# Eeprom.net
KiCad netlist of a schematic drawn in Altium Designer
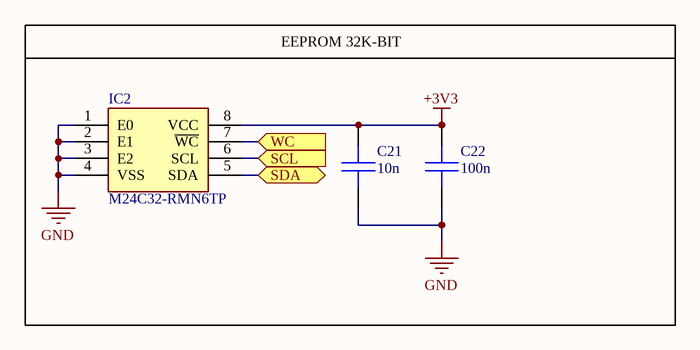
[diagram p0: Eeprom.SchDoc]

(export (version "E")
  (design (tool "Eeschema 10.0.6"))
  (components
    (comp (ref "C21")
      (value "10n")
      (footprint "C_0603")
      (description "SMD Chip Capacitor")
      (libsource (lib "My_Integrated_Lib") (part "CAP"))
    )
    (comp (ref "C22")
      (value "100n")
      (footprint "C_0603")
      (description "SMD Chip Capacitor")
      (libsource (lib "My_Integrated_Lib") (part "CAP"))
    )
    (comp (ref "IC2")
      (value "M24C32-RMN6TP")
      (footprint "SOIC127P600X175-8N")
      (description "Integrated Circuit")
      (fields (field (name "MOUSER PART NUMBER") "511-M24C32-RMN6TP"))
      (libsource (lib "My_Integrated_Lib") (part "M24C32-RMN6TP"))
    )
  )
  (nets
    (net (code "1") (name "+3V3") (class "Default")
      (node (ref "C21") (pin "1") (pinfunction "1_1") (pintype "passive"))
      (node (ref "C22") (pin "1") (pinfunction "1_1") (pintype "passive"))
      (node (ref "IC2") (pin "8") (pinfunction "VCC_8") (pintype "passive"))
    )
    (net (code "2") (name "/SCL") (class "Default")
      (node (ref "IC2") (pin "6") (pinfunction "SCL_6") (pintype "passive"))
    )
    (net (code "3") (name "/SDA") (class "Default")
      (node (ref "IC2") (pin "5") (pinfunction "SDA_5") (pintype "passive"))
    )
    (net (code "4") (name "/WC") (class "Default")
      (node (ref "IC2") (pin "7") (pinfunction "~{WC}_7") (pintype "passive"))
    )
    (net (code "5") (name "GND") (class "Default")
      (node (ref "C21") (pin "2") (pinfunction "2_2") (pintype "passive"))
      (node (ref "C22") (pin "2") (pinfunction "2_2") (pintype "passive"))
      (node (ref "IC2") (pin "1") (pinfunction "E0_1") (pintype "passive"))
      (node (ref "IC2") (pin "2") (pinfunction "E1_2") (pintype "passive"))
      (node (ref "IC2") (pin "3") (pinfunction "E2_3") (pintype "passive"))
      (node (ref "IC2") (pin "4") (pinfunction "VSS_4") (pintype "passive"))
    )
  )
)
